# MB1312.net
KiCad netlist of a schematic drawn in Altium Designer
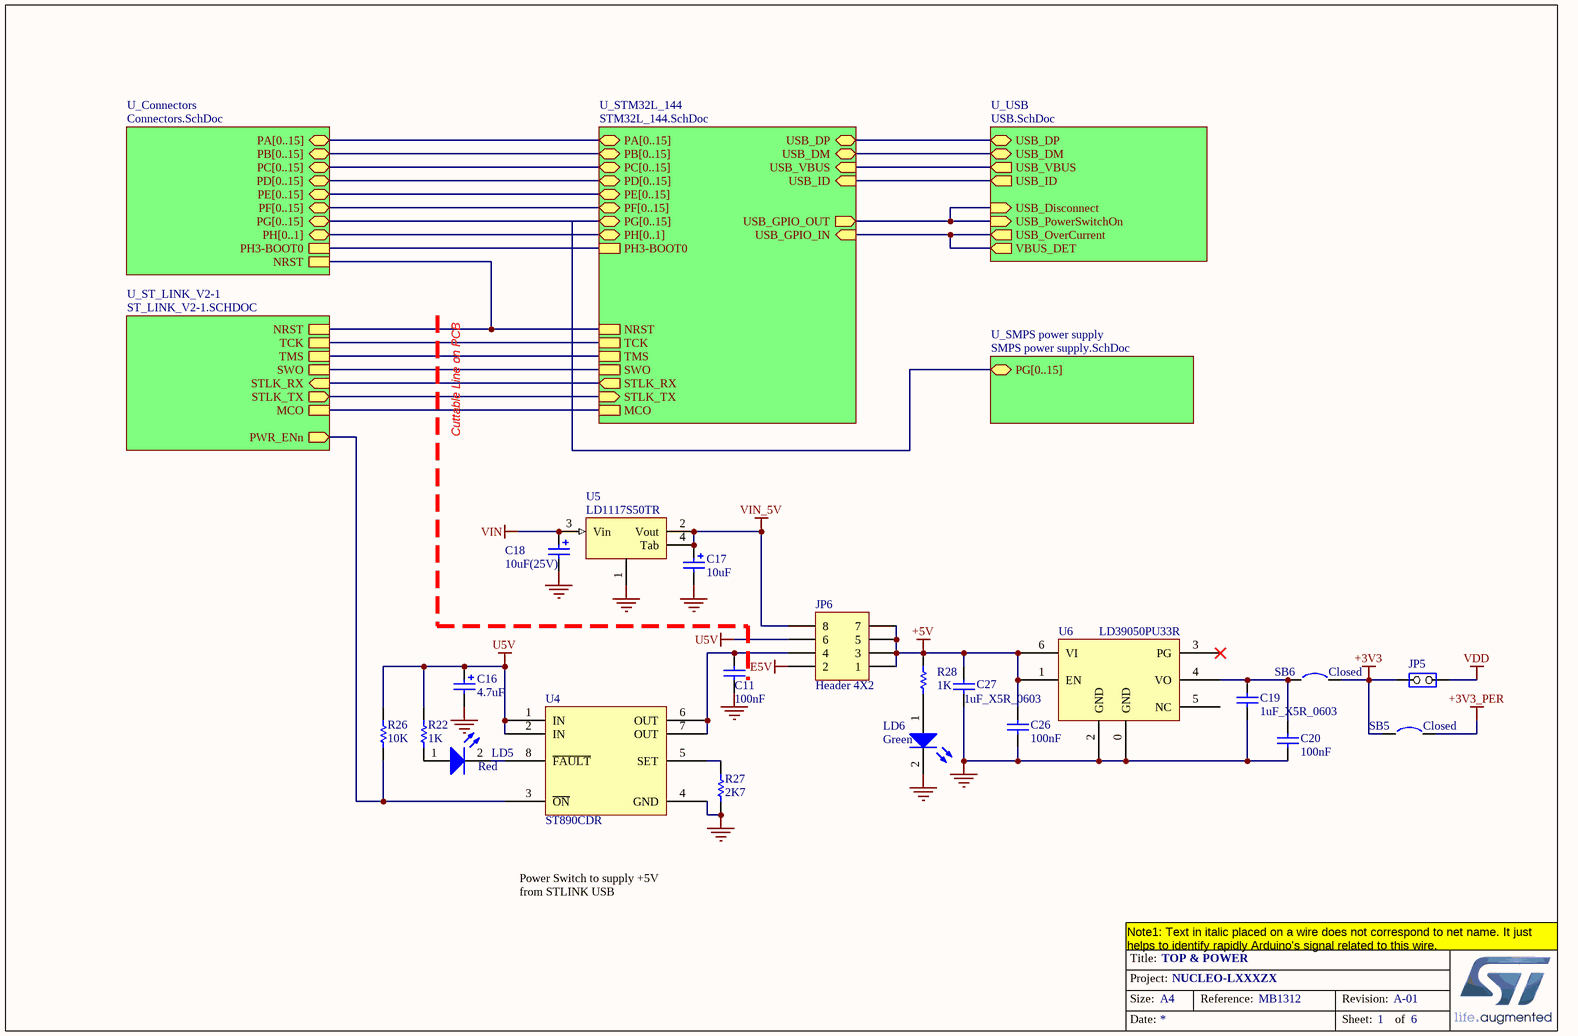
[diagram p0: MB1312.SchDoc]

(export (version "E")
  (design (tool "Eeschema 10.0.6"))
  (components
    (comp (ref "C11")
      (value "100nF")
      (footprint "0603C")
      (description "Capacitor 0402 / 0603 / 0805")
      (libsource (lib "MCD_TOOLS") (part "Capacitor_ST"))
    )
    (comp (ref "C16")
      (value "4.7uF")
      (footprint "TAN-A")
      (description "Polarized Capacitor (Radial)")
      (fields (field (name "PUBLISHER") "Altium Limited"))
      (libsource (lib "*") (part "Cap Pol1"))
    )
    (comp (ref "C17")
      (value "10uF")
      (footprint "TAN-A")
      (description "Polarized Capacitor (Radial)")
      (fields (field (name "PUBLISHER") "Altium Limited"))
      (libsource (lib "Miscellaneous Devices") (part "Cap Pol1"))
    )
    (comp (ref "C18")
      (value "10uF(25V)")
      (footprint "TAN-B")
      (description "Polarized Capacitor (Radial)")
      (fields (field (name "PUBLISHER") "Altium Limited"))
      (libsource (lib "Miscellaneous Devices") (part "Cap Pol1"))
    )
    (comp (ref "C19")
      (value "1uF_X5R_0603")
      (footprint "0603C")
      (description "0603  X5R 1µF")
      (fields (field (name "TOLERANCE") "10%"))
      (libsource (lib "MB963_1") (part "CAP SMD 0603  X5R 1µF 25V 10%"))
    )
    (comp (ref "C20")
      (value "100nF")
      (footprint "0603C")
      (description "Capacitor 0402 / 0603 / 0805")
      (libsource (lib "MCD_TOOLS") (part "Capacitor_ST"))
    )
    (comp (ref "C26")
      (value "100nF")
      (footprint "0603C")
      (description "Capacitor 0402 / 0603 / 0805")
      (libsource (lib "MCD_TOOLS") (part "Capacitor_ST"))
    )
    (comp (ref "C27")
      (value "1uF_X5R_0603")
      (footprint "0603C")
      (description "0603  X5R 1µF")
      (fields (field (name "TOLERANCE") "10%"))
      (libsource (lib "MB963_1") (part "CAP SMD 0603  X5R 1µF 25V 10%"))
    )
    (comp (ref "JP5") (value "~") (footprint "HDR_1x2_2R54_V_M_S") (libsource (lib "*") (part "JP2")))
    (comp (ref "JP6")
      (value "Header 4X2")
      (footprint "HDR_4x2_2R54_V_M")
      (description "Header, 4-Pin, Dual row")
      (fields (field (name "PUBLISHER") "Altium Limited"))
      (libsource (lib "MB1312") (part "Header 4X2"))
    )
    (comp (ref "LD5")
      (value "Red")
      (footprint "0603D-R")
      (description "Typical RED, GREEN, YELLOW, AMBER GaAs LED")
      (fields (field (name "PUBLISHER") "Altium Limited"))
      (libsource (lib "") (part "LED2_1"))
    )
    (comp (ref "LD6")
      (value "Green")
      (footprint "0603D-G")
      (description "Typical RED, GREEN, YELLOW, AMBER GaAs LED")
      (fields (field (name "PUBLISHER") "Altium Limited"))
      (libsource (lib "Miscellaneous Devices") (part "LED2"))
    )
    (comp (ref "R22")
      (value "1K")
      (footprint "0603R")
      (description "Resistor")
      (fields (field (name "PUBLISHER") "Altium Limited"))
      (libsource (lib "*") (part "Res1"))
    )
    (comp (ref "R26")
      (value "10K")
      (footprint "STM-SMEE:0603R")
      (description "Resistor 0402 or 0603 or 0805")
      (libsource (lib "MCD_TOOLS") (part "Resistor_ST"))
    )
    (comp (ref "R27")
      (value "2K7")
      (footprint "STM-SMEE:0603R")
      (description "Resistor 0402 or 0603 or 0805")
      (libsource (lib "MCD_TOOLS") (part "Resistor_ST"))
    )
    (comp (ref "R28")
      (value "1K")
      (footprint "0603R")
      (description "Resistor 0402 or 0603 or 0805")
      (libsource (lib "MCD_TOOLS") (part "Resistor_ST"))
    )
    (comp (ref "SB5")
      (value "Closed")
      (footprint "SB_0603")
      (description "Circuit Breaker")
      (fields (field (name "PUBLISHER") "Altium Limited"))
      (libsource (lib "MB1167") (part "Circuit Breaker_close"))
    )
    (comp (ref "SB6")
      (value "Closed")
      (footprint "SB_0603")
      (description "Circuit Breaker")
      (fields (field (name "PUBLISHER") "Altium Limited"))
      (libsource (lib "MB1167") (part "Circuit Breaker_close"))
    )
    (comp (ref "U4")
      (value "ST890CDR")
      (footprint "SOIC8_1R27_4R9X6")
      (libsource (lib "MB1137") (part "ST890CDR"))
    )
    (comp (ref "U5") (value "LD1117S50TR") (footprint "SOT-223") (libsource (lib "MB1137") (part "LD1117")))
    (comp (ref "U6")
      (value "LD39050PU33R")
      (footprint "DFN6_0R95_3x3_TP")
      (libsource (lib "MB1137") (part "LD39050P"))
    )
  )
  (nets
    (net (code "1") (name "+3V3") (class "Default")
      (node (ref "JP5") (pin "1") (pinfunction "COMMON_1") (pintype "passive"))
      (node (ref "SB5") (pin "1") (pinfunction "1_1") (pintype "passive"))
      (node (ref "SB6") (pin "2") (pinfunction "2_2") (pintype "passive"))
    )
    (net (code "2") (name "+3V3_PER") (class "Default")
      (node (ref "SB5") (pin "2") (pinfunction "2_2") (pintype "passive"))
    )
    (net (code "3") (name "+5V") (class "Default")
      (node (ref "C26") (pin "2") (pinfunction "2_2") (pintype "passive"))
      (node (ref "C27") (pin "1") (pinfunction "1_1") (pintype "passive"))
      (node (ref "JP6") (pin "1") (pinfunction "1_1") (pintype "passive"))
      (node (ref "JP6") (pin "3") (pinfunction "3_3") (pintype "passive"))
      (node (ref "JP6") (pin "5") (pinfunction "5_5") (pintype "passive"))
      (node (ref "JP6") (pin "7") (pinfunction "7_7") (pintype "passive"))
      (node (ref "R28") (pin "2") (pinfunction "2_2") (pintype "passive"))
      (node (ref "U6") (pin "1") (pinfunction "EN_1") (pintype "passive"))
      (node (ref "U6") (pin "6") (pinfunction "VI_6") (pintype "passive"))
    )
    (net (code "16") (name "/PWR_ENn") (class "Default")
      (node (ref "R26") (pin "2") (pinfunction "2_2") (pintype "passive"))
      (node (ref "U4") (pin "3") (pinfunction "~{ON}_3") (pintype "passive"))
    )
    (net (code "28") (name "E5V") (class "Default")
      (node (ref "JP6") (pin "2") (pinfunction "2_2") (pintype "passive"))
    )
    (net (code "29") (name "GND") (class "Default")
      (node (ref "C11") (pin "1") (pinfunction "1_1") (pintype "passive"))
      (node (ref "C16") (pin "2") (pinfunction "2_2") (pintype "passive"))
      (node (ref "C17") (pin "2") (pinfunction "2_2") (pintype "passive"))
      (node (ref "C18") (pin "2") (pinfunction "2_2") (pintype "passive"))
      (node (ref "C19") (pin "2") (pinfunction "2_2") (pintype "passive"))
      (node (ref "C20") (pin "1") (pinfunction "1_1") (pintype "passive"))
      (node (ref "C26") (pin "1") (pinfunction "1_1") (pintype "passive"))
      (node (ref "C27") (pin "2") (pinfunction "2_2") (pintype "passive"))
      (node (ref "LD6") (pin "2") (pinfunction "K_2") (pintype "passive"))
      (node (ref "R27") (pin "1") (pinfunction "1_1") (pintype "passive"))
      (node (ref "U4") (pin "4") (pinfunction "GND_4") (pintype "passive"))
      (node (ref "U5") (pin "1") (pintype "passive"))
      (node (ref "U6") (pin "0") (pinfunction "GND_0") (pintype "passive"))
      (node (ref "U6") (pin "2") (pinfunction "GND_2") (pintype "passive"))
    )
    (net (code "30") (name "Net-(C11-Pad2)") (class "Default")
      (node (ref "C11") (pin "2") (pinfunction "2_2") (pintype "passive"))
      (node (ref "JP6") (pin "4") (pinfunction "4_4") (pintype "passive"))
      (node (ref "U4") (pin "6") (pinfunction "OUT_6") (pintype "passive"))
      (node (ref "U4") (pin "7") (pinfunction "OUT_7") (pintype "passive"))
    )
    (net (code "31") (name "Net-(LD5-A)") (class "Default")
      (node (ref "LD5") (pin "1") (pinfunction "A_1") (pintype "passive"))
      (node (ref "R22") (pin "2") (pinfunction "2_2") (pintype "passive"))
    )
    (net (code "32") (name "Net-(LD5-K)") (class "Default")
      (node (ref "LD5") (pin "2") (pinfunction "K_2") (pintype "passive"))
      (node (ref "U4") (pin "8") (pinfunction "~{FAULT}_8") (pintype "passive"))
    )
    (net (code "33") (name "Net-(LD6-A)") (class "Default")
      (node (ref "LD6") (pin "1") (pinfunction "A_1") (pintype "passive"))
      (node (ref "R28") (pin "1") (pinfunction "1_1") (pintype "passive"))
    )
    (net (code "34") (name "Net-(U4-SET)") (class "Default")
      (node (ref "R27") (pin "2") (pinfunction "2_2") (pintype "passive"))
      (node (ref "U4") (pin "5") (pinfunction "SET_5") (pintype "passive"))
    )
    (net (code "35") (name "Net-(U6-VO)") (class "Default")
      (node (ref "C19") (pin "1") (pinfunction "1_1") (pintype "passive"))
      (node (ref "C20") (pin "2") (pinfunction "2_2") (pintype "passive"))
      (node (ref "SB6") (pin "1") (pinfunction "1_1") (pintype "passive"))
      (node (ref "U6") (pin "4") (pinfunction "VO_4") (pintype "passive"))
    )
    (net (code "36") (name "U5V") (class "Default")
      (node (ref "C16") (pin "1") (pinfunction "1_1") (pintype "passive"))
      (node (ref "JP6") (pin "6") (pinfunction "6_6") (pintype "passive"))
      (node (ref "R22") (pin "1") (pinfunction "1_1") (pintype "passive"))
      (node (ref "R26") (pin "1") (pinfunction "1_1") (pintype "passive"))
      (node (ref "U4") (pin "1") (pinfunction "IN_1") (pintype "passive"))
      (node (ref "U4") (pin "2") (pinfunction "IN_2") (pintype "passive"))
    )
    (net (code "37") (name "VDD") (class "Default")
      (node (ref "JP5") (pin "2") (pinfunction "NO_2") (pintype "passive"))
    )
    (net (code "38") (name "VIN") (class "Default")
      (node (ref "C18") (pin "1") (pinfunction "1_1") (pintype "passive"))
      (node (ref "U5") (pin "3") (pinfunction "Vin_3") (pintype "input"))
    )
    (net (code "39") (name "VIN_5V") (class "Default")
      (node (ref "C17") (pin "1") (pinfunction "1_1") (pintype "passive"))
      (node (ref "JP6") (pin "8") (pinfunction "8_8") (pintype "passive"))
      (node (ref "U5") (pin "2") (pinfunction "Vout_2") (pintype "power_in"))
      (node (ref "U5") (pin "4") (pinfunction "Tab_4") (pintype "power_in"))
    )
    (net (code "40") (name "unconnected-(U6-NC-Pad5)") (class "Default")
      (node (ref "U6") (pin "5") (pinfunction "NC_5") (pintype "passive"))
    )
    (net (code "41") (name "unconnected-(U6-PG-Pad3)") (class "Default")
      (node (ref "U6") (pin "3") (pinfunction "PG_3") (pintype "passive+no_connect"))
    )
  )
)
